# PAGE2_-MCU.net
KiCad netlist of a schematic drawn in Altium Designer
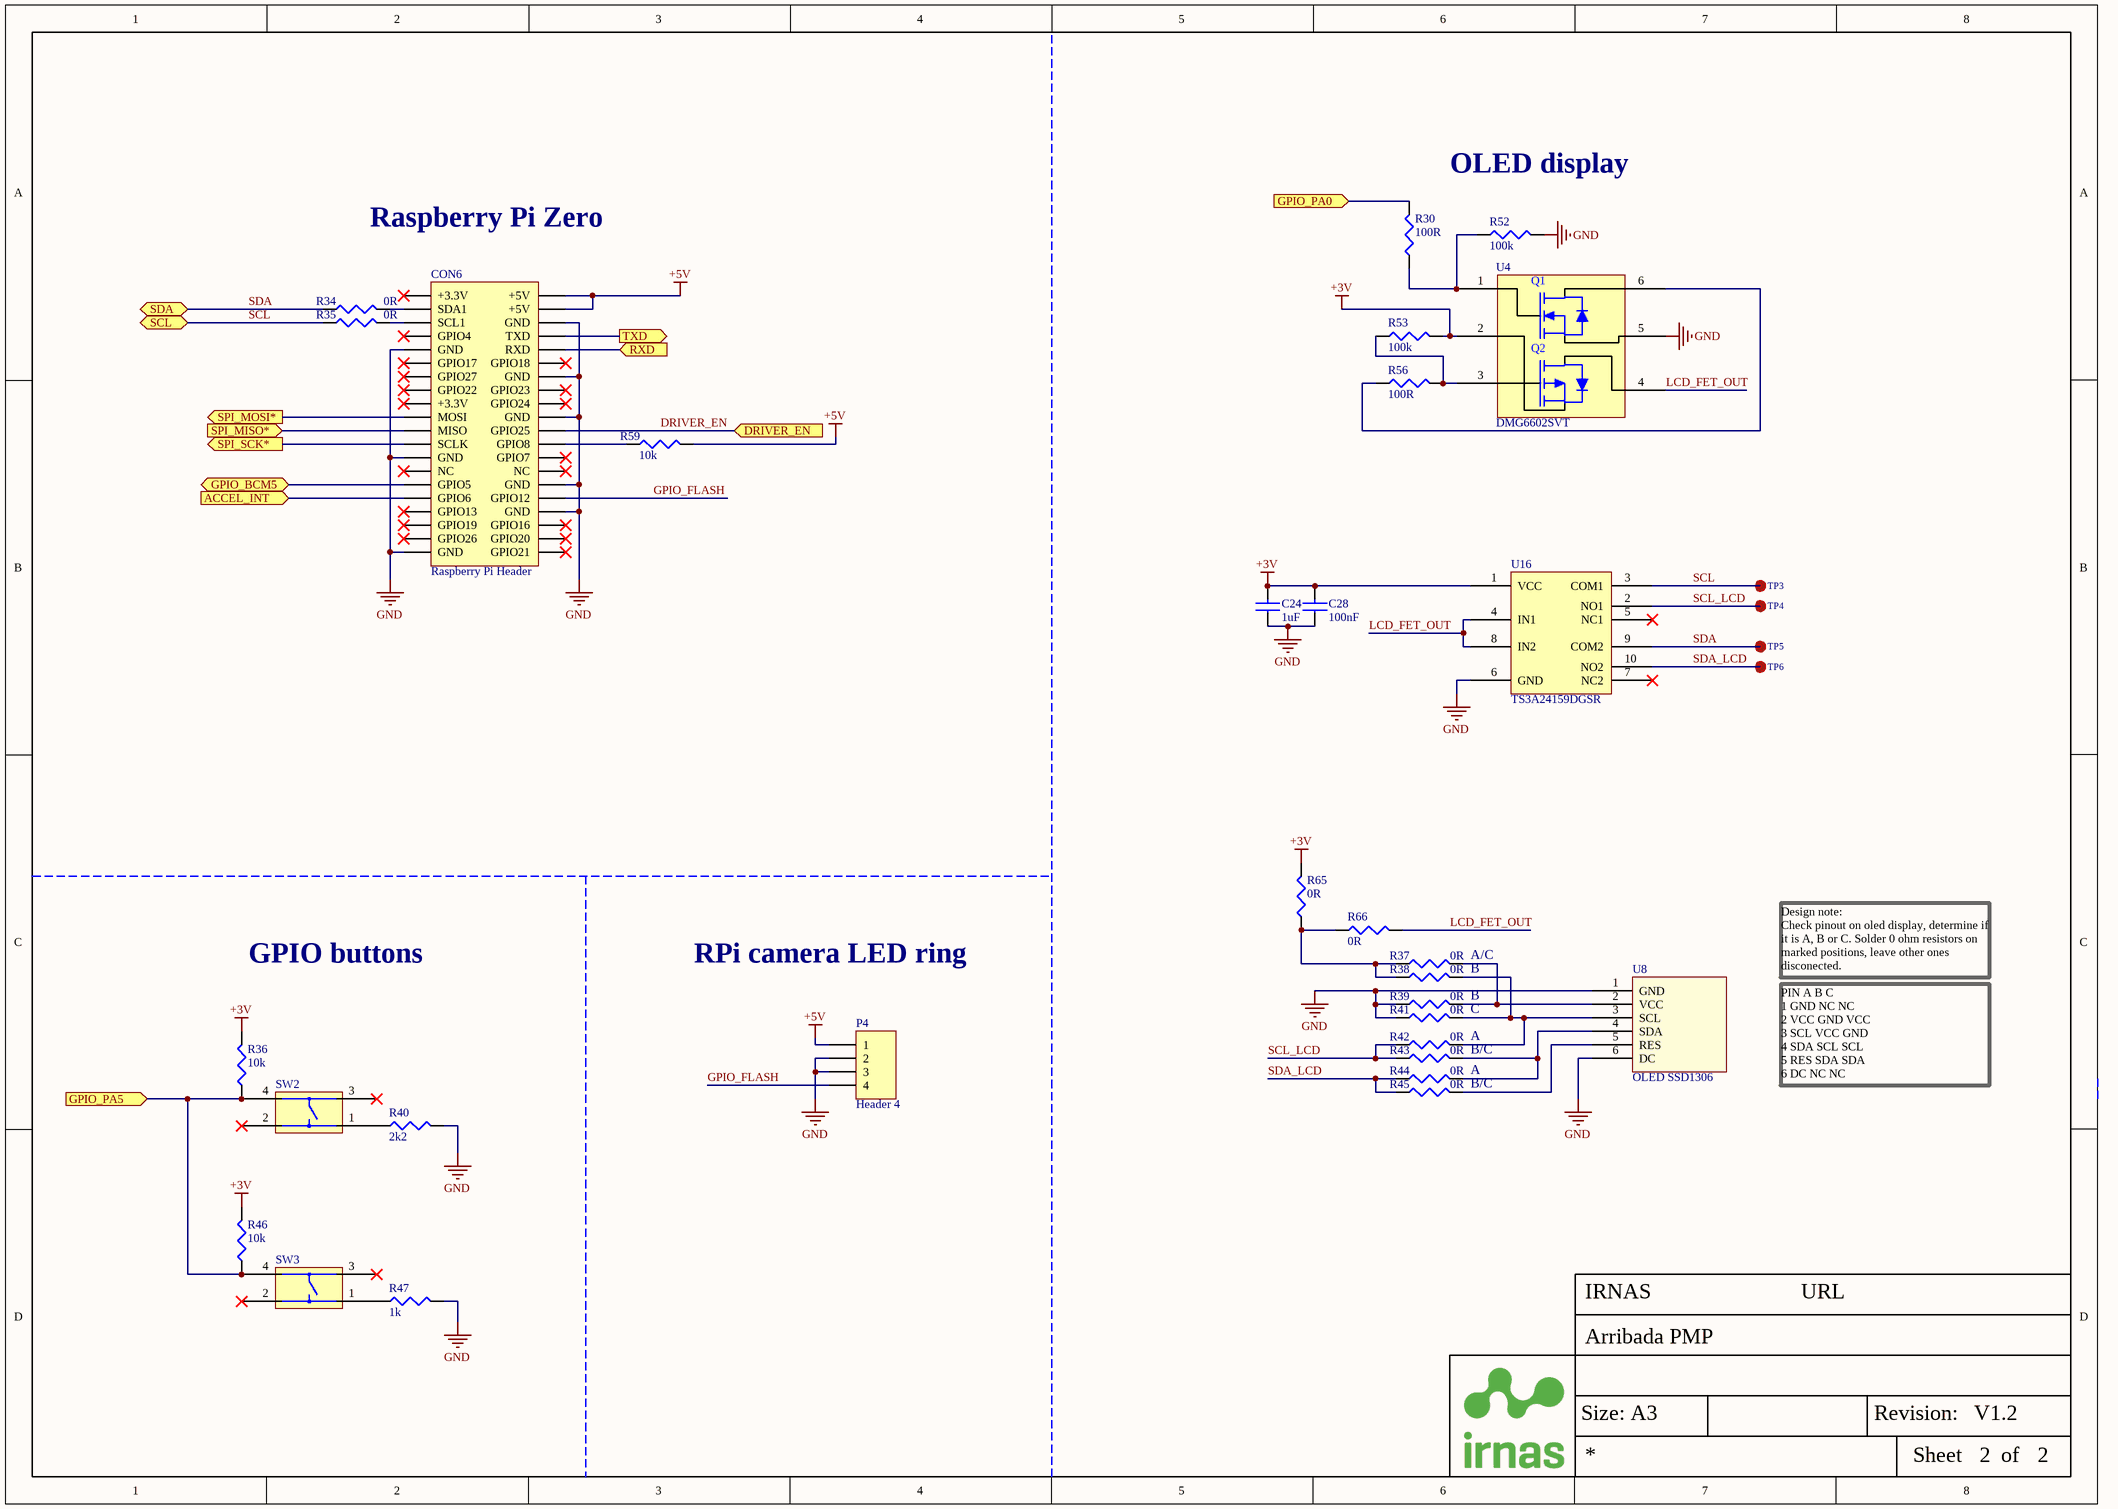
[diagram p0: PAGE2 -MCU.SchDoc]

(export (version "E")
  (design (tool "Eeschema 10.0.6"))
  (components
    (comp (ref "C24")
      (value "1uF")
      (footprint "CAP0603")
      (description "MURATA - GRM188R61H105KAALD - CAP, MLCC, X5R, 1UF, 50V, 0603")
      (fields
        (field (name "MANUFACTURER") "MURATA")
        (field (name "MANUFACTURER PART NUMBER") "GRM188R61H105KAALD")
      )
      (libsource (lib "Passive") (part "C - 1uF"))
    )
    (comp (ref "C28")
      (value "100nF")
      (footprint "CAP0603")
      (description "MURATA - GRM188R71C104KA01J - CAP, MLCC, X7R, 0.1UF, 16V, 0603")
      (fields
        (field (name "MANUFACTURER") "MURATA")
        (field (name "MANUFACTURER PART NUMBER") "GRM188R71C104KA01J")
      )
      (libsource (lib "Passive") (part "C - 100nF"))
    )
    (comp (ref "CON6")
      (value "Raspberry Pi Header")
      (footprint "Connectors:HDR2X20")
      (description "Header, 20-Pin, Dual row")
      (fields (field (name "PUBLISHER") "Altium Limited"))
      (libsource (lib "Connectors") (part "Raspberry Pi Header"))
    )
    (comp (ref "P4")
      (value "Header 4")
      (footprint "HDR1X4")
      (description "Header, 4-Pin")
      (fields (field (name "PUBLISHER") "Altium Limited"))
      (libsource (lib "Miscellaneous Connectors") (part "Header 4"))
    )
    (comp (ref "R30")
      (value "100R")
      (footprint "RES0603")
      (description "MULTICOMP - MC0063W06031100R - RES, THICK FILM, 100R, 1%, 0.063W, 0603")
      (fields
        (field (name "MANUFACTURER") "MULTICOMP")
        (field (name "MANUFACTURER PART NUMBER") "MC0063W06031100R")
      )
      (libsource (lib "Passive") (part "R - 100R"))
    )
    (comp (ref "R34")
      (value "0R")
      (footprint "RES0603")
      (description "BOURNS - CR0603-J/-000ELF - RES, THICK FILM, 0R, 5%, 0.1W, 0603")
      (fields
        (field (name "MANUFACTURER") "BOURNS")
        (field (name "MANUFACTURER PART NUMBER") "CR0603-J/-000ELF")
      )
      (libsource (lib "Passive") (part "R - 0R"))
    )
    (comp (ref "R35")
      (value "0R")
      (footprint "RES0603")
      (description "BOURNS - CR0603-J/-000ELF - RES, THICK FILM, 0R, 5%, 0.1W, 0603")
      (fields
        (field (name "MANUFACTURER") "BOURNS")
        (field (name "MANUFACTURER PART NUMBER") "CR0603-J/-000ELF")
      )
      (libsource (lib "Passive") (part "R - 0R"))
    )
    (comp (ref "R36")
      (value "10k")
      (footprint "RES0603")
      (description "MULTICOMP - MCMR06X103 JTL - RES, CERAMIC, 10K, 5%, 0.1W, 0603")
      (fields
        (field (name "MANUFACTURER") "MULTICOMP")
        (field (name "MANUFACTURER PART NUMBER") "MCMR06X103 JTL")
      )
      (libsource (lib "Passive") (part "R - 10k"))
    )
    (comp (ref "R37")
      (value "0R")
      (footprint "RES0603")
      (description "BOURNS - CR0603-J/-000ELF - RES, THICK FILM, 0R, 5%, 0.1W, 0603")
      (fields
        (field (name "MANUFACTURER") "BOURNS")
        (field (name "MANUFACTURER PART NUMBER") "CR0603-J/-000ELF")
      )
      (libsource (lib "Passive") (part "R - 0R"))
    )
    (comp (ref "R38")
      (value "0R")
      (footprint "RES0603")
      (description "BOURNS - CR0603-J/-000ELF - RES, THICK FILM, 0R, 5%, 0.1W, 0603")
      (fields
        (field (name "MANUFACTURER") "BOURNS")
        (field (name "MANUFACTURER PART NUMBER") "CR0603-J/-000ELF")
      )
      (libsource (lib "Passive") (part "R - 0R"))
    )
    (comp (ref "R39")
      (value "0R")
      (footprint "RES0603")
      (description "BOURNS - CR0603-J/-000ELF - RES, THICK FILM, 0R, 5%, 0.1W, 0603")
      (fields
        (field (name "MANUFACTURER") "BOURNS")
        (field (name "MANUFACTURER PART NUMBER") "CR0603-J/-000ELF")
      )
      (libsource (lib "Passive") (part "R - 0R"))
    )
    (comp (ref "R40")
      (value "2k2")
      (footprint "RES0603")
      (description "MULTICOMP - MCMR06X2201FTL - RES, CERAMIC, 2K2, 1%, 0.1W, 0603")
      (fields
        (field (name "MANUFACTURER") "MULTICOMP")
        (field (name "MANUFACTURER PART NUMBER") "MCMR06X2201FTL")
      )
      (libsource (lib "Passive") (part "R - 2k2"))
    )
    (comp (ref "R41")
      (value "0R")
      (footprint "RES0603")
      (description "BOURNS - CR0603-J/-000ELF - RES, THICK FILM, 0R, 5%, 0.1W, 0603")
      (fields
        (field (name "MANUFACTURER") "BOURNS")
        (field (name "MANUFACTURER PART NUMBER") "CR0603-J/-000ELF")
      )
      (libsource (lib "Passive") (part "R - 0R"))
    )
    (comp (ref "R42")
      (value "0R")
      (footprint "RES0603")
      (description "BOURNS - CR0603-J/-000ELF - RES, THICK FILM, 0R, 5%, 0.1W, 0603")
      (fields
        (field (name "MANUFACTURER") "BOURNS")
        (field (name "MANUFACTURER PART NUMBER") "CR0603-J/-000ELF")
      )
      (libsource (lib "Passive") (part "R - 0R"))
    )
    (comp (ref "R43")
      (value "0R")
      (footprint "RES0603")
      (description "BOURNS - CR0603-J/-000ELF - RES, THICK FILM, 0R, 5%, 0.1W, 0603")
      (fields
        (field (name "MANUFACTURER") "BOURNS")
        (field (name "MANUFACTURER PART NUMBER") "CR0603-J/-000ELF")
      )
      (libsource (lib "Passive") (part "R - 0R"))
    )
    (comp (ref "R44")
      (value "0R")
      (footprint "RES0603")
      (description "BOURNS - CR0603-J/-000ELF - RES, THICK FILM, 0R, 5%, 0.1W, 0603")
      (fields
        (field (name "MANUFACTURER") "BOURNS")
        (field (name "MANUFACTURER PART NUMBER") "CR0603-J/-000ELF")
      )
      (libsource (lib "Passive") (part "R - 0R"))
    )
    (comp (ref "R45")
      (value "0R")
      (footprint "RES0603")
      (description "BOURNS - CR0603-J/-000ELF - RES, THICK FILM, 0R, 5%, 0.1W, 0603")
      (fields
        (field (name "MANUFACTURER") "BOURNS")
        (field (name "MANUFACTURER PART NUMBER") "CR0603-J/-000ELF")
      )
      (libsource (lib "Passive") (part "R - 0R"))
    )
    (comp (ref "R46")
      (value "10k")
      (footprint "RES0603")
      (description "MULTICOMP - MCMR06X103 JTL - RES, CERAMIC, 10K, 5%, 0.1W, 0603")
      (fields
        (field (name "MANUFACTURER") "MULTICOMP")
        (field (name "MANUFACTURER PART NUMBER") "MCMR06X103 JTL")
      )
      (libsource (lib "Passive") (part "R - 10k"))
    )
    (comp (ref "R47")
      (value "1k")
      (footprint "RES0603")
      (description "MULTICOMP - MCMR06X102 JTL - RES, CERAMIC, 1K, 5%, 0.1W, 0603")
      (fields
        (field (name "MANUFACTURER") "MULTICOMP")
        (field (name "MANUFACTURER PART NUMBER") "MCMR06X102 JTL")
      )
      (libsource (lib "Passive") (part "R - 1k"))
    )
    (comp (ref "R52")
      (value "100k")
      (footprint "RES0603")
      (description "MULTICOMP - MCMR06X104 JTL - RES, CERAMIC, 100K, 5%, 0.1W, 0603")
      (fields
        (field (name "MANUFACTURER") "MULTICOMP")
        (field (name "MANUFACTURER PART NUMBER") "MCMR06X104 JTL")
      )
      (libsource (lib "Passive") (part "R - 100k"))
    )
    (comp (ref "R53")
      (value "100k")
      (footprint "RES0603")
      (description "MULTICOMP - MCMR06X104 JTL - RES, CERAMIC, 100K, 5%, 0.1W, 0603")
      (fields
        (field (name "MANUFACTURER") "MULTICOMP")
        (field (name "MANUFACTURER PART NUMBER") "MCMR06X104 JTL")
      )
      (libsource (lib "Passive") (part "R - 100k"))
    )
    (comp (ref "R56")
      (value "100R")
      (footprint "RES0603")
      (description "MULTICOMP - MC0063W06031100R - RES, THICK FILM, 100R, 1%, 0.063W, 0603")
      (fields
        (field (name "MANUFACTURER") "MULTICOMP")
        (field (name "MANUFACTURER PART NUMBER") "MC0063W06031100R")
      )
      (libsource (lib "Passive") (part "R - 100R"))
    )
    (comp (ref "R59")
      (value "10k")
      (footprint "RES0603")
      (description "MULTICOMP - MCMR06X103 JTL - RES, CERAMIC, 10K, 5%, 0.1W, 0603")
      (fields
        (field (name "MANUFACTURER") "MULTICOMP")
        (field (name "MANUFACTURER PART NUMBER") "MCMR06X103 JTL")
      )
      (libsource (lib "Passive") (part "R - 10k"))
    )
    (comp (ref "R65")
      (value "0R")
      (footprint "RES0603")
      (description "BOURNS - CR0603-J/-000ELF - RES, THICK FILM, 0R, 5%, 0.1W, 0603")
      (fields
        (field (name "MANUFACTURER") "BOURNS")
        (field (name "MANUFACTURER PART NUMBER") "CR0603-J/-000ELF")
      )
      (libsource (lib "Passive") (part "R - 0R"))
    )
    (comp (ref "R66")
      (value "0R")
      (footprint "RES0603")
      (description "BOURNS - CR0603-J/-000ELF - RES, THICK FILM, 0R, 5%, 0.1W, 0603")
      (fields
        (field (name "MANUFACTURER") "BOURNS")
        (field (name "MANUFACTURER PART NUMBER") "CR0603-J/-000ELF")
      )
      (libsource (lib "Passive") (part "R - 0R"))
    )
    (comp (ref "SW2")
      (value "BTN - B3F-1070")
      (footprint "BTN B3F-1070")
      (description "Tactile Switch, B3F Series, Top Actuated, Through Hole, Round Button, 100 gf, 50mA at 24VDC")
      (libsource (lib "Mechanical") (part "BTN - B3F-1070"))
    )
    (comp (ref "SW3")
      (value "BTN - B3F-1070")
      (footprint "BTN B3F-1070")
      (description "Tactile Switch, B3F Series, Top Actuated, Through Hole, Round Button, 100 gf, 50mA at 24VDC")
      (libsource (lib "Mechanical") (part "BTN - B3F-1070"))
    )
    (comp (ref "TP3")
      (value "TestPoint")
      (footprint "Passive:TestPoint:1.2x1.2mm")
      (description "TEST POINT ROUND SMD")
      (libsource (lib "Passive") (part "TestPoint"))
    )
    (comp (ref "TP4")
      (value "TestPoint")
      (footprint "Passive:TestPoint:1.2x1.2mm")
      (description "TEST POINT ROUND SMD")
      (libsource (lib "Passive") (part "TestPoint"))
    )
    (comp (ref "TP5")
      (value "TestPoint")
      (footprint "Passive:TestPoint:1.2x1.2mm")
      (description "TEST POINT ROUND SMD")
      (libsource (lib "Passive") (part "TestPoint"))
    )
    (comp (ref "TP6")
      (value "TestPoint")
      (footprint "Passive:TestPoint:1.2x1.2mm")
      (description "TEST POINT ROUND SMD")
      (libsource (lib "Passive") (part "TestPoint"))
    )
    (comp (ref "U4")
      (value "DMG6602SVT")
      (footprint "TSOT26")
      (description "Dual MOSFET, N and P Channel, 3.4 A, 30 V, 0.038 ohm, 10 V, 1 V")
      (libsource (lib "Active") (part "T_M - DMG6602SVT"))
    )
    (comp (ref "U8")
      (value "OLED SSD1306")
      (footprint "OLED SSD1306")
      (libsource (lib "oled") (part "OLED SSD1306"))
    )
    (comp (ref "U16")
      (value "TS3A24159DGSR")
      (footprint "VSSOP-10")
      (description "Analogue Switch, 2 Channels, SPDT, 0.34 ohm, 1.65V to 3.6V, VSSOP, 10 Pins")
      (libsource (lib "Active") (part "INT - TS3A24159DGSR"))
    )
  )
  (nets
    (net (code "1") (name "+3V") (class "Default")
      (node (ref "C24") (pin "2") (pinfunction "2_2") (pintype "passive"))
      (node (ref "C28") (pin "2") (pinfunction "2_2") (pintype "passive"))
      (node (ref "R36") (pin "2") (pinfunction "2_2") (pintype "passive"))
      (node (ref "R46") (pin "2") (pinfunction "2_2") (pintype "passive"))
      (node (ref "R53") (pin "2") (pinfunction "2_2") (pintype "passive"))
      (node (ref "R65") (pin "2") (pinfunction "2_2") (pintype "passive"))
      (node (ref "U16") (pin "1") (pinfunction "VCC_1") (pintype "passive"))
      (node (ref "U4") (pin "2") (pinfunction "S2_2") (pintype "open_collector"))
    )
    (net (code "2") (name "+5V") (class "Default")
      (node (ref "CON6") (pin "2") (pinfunction "+5V_2") (pintype "passive"))
      (node (ref "CON6") (pin "4") (pinfunction "+5V_4") (pintype "passive"))
      (node (ref "P4") (pin "1") (pinfunction "1_1") (pintype "passive"))
      (node (ref "R59") (pin "2") (pinfunction "2_2") (pintype "passive"))
    )
    (net (code "3") (name "/ACCEL_INT") (class "Default")
      (node (ref "CON6") (pin "31") (pinfunction "GPIO6_31") (pintype "passive"))
    )
    (net (code "4") (name "/DRIVER_EN") (class "Default")
      (node (ref "CON6") (pin "22") (pinfunction "GPIO25_22") (pintype "passive"))
    )
    (net (code "5") (name "/GPIO_BCM5") (class "Default")
      (node (ref "CON6") (pin "29") (pinfunction "GPIO5_29") (pintype "passive"))
    )
    (net (code "6") (name "/GPIO_FLASH") (class "Default")
      (node (ref "CON6") (pin "32") (pinfunction "GPIO12_32") (pintype "passive"))
      (node (ref "P4") (pin "4") (pinfunction "4_4") (pintype "passive"))
    )
    (net (code "7") (name "/GPIO_PA0") (class "Default")
      (node (ref "R30") (pin "2") (pinfunction "2_2") (pintype "passive"))
    )
    (net (code "8") (name "/GPIO_PA5") (class "Default")
      (node (ref "R36") (pin "1") (pinfunction "1_1") (pintype "passive"))
      (node (ref "R46") (pin "1") (pinfunction "1_1") (pintype "passive"))
      (node (ref "SW2") (pin "4") (pinfunction "4_4") (pintype "passive"))
      (node (ref "SW3") (pin "4") (pinfunction "4_4") (pintype "passive"))
    )
    (net (code "9") (name "/LCD_FET_OUT") (class "Default")
      (node (ref "R66") (pin "2") (pinfunction "2_2") (pintype "passive"))
      (node (ref "U16") (pin "4") (pinfunction "IN1_4") (pintype "passive"))
      (node (ref "U16") (pin "8") (pinfunction "IN2_8") (pintype "passive"))
      (node (ref "U4") (pin "4") (pinfunction "D2_4") (pintype "open_collector"))
    )
    (net (code "10") (name "/RXD") (class "Default")
      (node (ref "CON6") (pin "10") (pinfunction "RXD_10") (pintype "passive"))
    )
    (net (code "11") (name "/SCL") (class "Default")
      (node (ref "R35") (pin "1") (pinfunction "1_1") (pintype "passive"))
      (node (ref "TP3") (pin "0") (pinfunction "0_0") (pintype "passive"))
      (node (ref "U16") (pin "3") (pinfunction "COM1_3") (pintype "passive"))
    )
    (net (code "12") (name "/SCL_LCD") (class "Default")
      (node (ref "R42") (pin "1") (pinfunction "1_1") (pintype "passive"))
      (node (ref "R43") (pin "1") (pinfunction "1_1") (pintype "passive"))
      (node (ref "TP4") (pin "0") (pinfunction "0_0") (pintype "passive"))
      (node (ref "U16") (pin "2") (pinfunction "NO1_2") (pintype "passive"))
    )
    (net (code "13") (name "/SDA") (class "Default")
      (node (ref "R34") (pin "1") (pinfunction "1_1") (pintype "passive"))
      (node (ref "TP5") (pin "0") (pinfunction "0_0") (pintype "passive"))
      (node (ref "U16") (pin "9") (pinfunction "COM2_9") (pintype "passive"))
    )
    (net (code "14") (name "/SDA_LCD") (class "Default")
      (node (ref "R44") (pin "1") (pinfunction "1_1") (pintype "passive"))
      (node (ref "R45") (pin "1") (pinfunction "1_1") (pintype "passive"))
      (node (ref "TP6") (pin "0") (pinfunction "0_0") (pintype "passive"))
      (node (ref "U16") (pin "10") (pinfunction "NO2_10") (pintype "passive"))
    )
    (net (code "15") (name "/SPI_MISO*") (class "Default")
      (node (ref "CON6") (pin "21") (pinfunction "MISO_21") (pintype "passive"))
    )
    (net (code "16") (name "/SPI_MOSI*") (class "Default")
      (node (ref "CON6") (pin "19") (pinfunction "MOSI_19") (pintype "passive"))
    )
    (net (code "17") (name "/SPI_SCK*") (class "Default")
      (node (ref "CON6") (pin "23") (pinfunction "SCLK_23") (pintype "passive"))
    )
    (net (code "18") (name "/TXD") (class "Default")
      (node (ref "CON6") (pin "8") (pinfunction "TXD_8") (pintype "passive"))
    )
    (net (code "19") (name "GND") (class "Default")
      (node (ref "C24") (pin "1") (pinfunction "1_1") (pintype "passive"))
      (node (ref "C28") (pin "1") (pinfunction "1_1") (pintype "passive"))
      (node (ref "CON6") (pin "14") (pinfunction "GND_14") (pintype "passive"))
      (node (ref "CON6") (pin "20") (pinfunction "GND_20") (pintype "passive"))
      (node (ref "CON6") (pin "25") (pinfunction "GND_25") (pintype "passive"))
      (node (ref "CON6") (pin "30") (pinfunction "GND_30") (pintype "passive"))
      (node (ref "CON6") (pin "34") (pinfunction "GND_34") (pintype "passive"))
      (node (ref "CON6") (pin "39") (pinfunction "GND_39") (pintype "passive"))
      (node (ref "CON6") (pin "6") (pinfunction "GND_6") (pintype "passive"))
      (node (ref "CON6") (pin "9") (pinfunction "GND_9") (pintype "passive"))
      (node (ref "P4") (pin "2") (pinfunction "2_2") (pintype "passive"))
      (node (ref "P4") (pin "3") (pinfunction "3_3") (pintype "passive"))
      (node (ref "R39") (pin "1") (pinfunction "1_1") (pintype "passive"))
      (node (ref "R40") (pin "2") (pinfunction "2_2") (pintype "passive"))
      (node (ref "R41") (pin "1") (pinfunction "1_1") (pintype "passive"))
      (node (ref "R47") (pin "2") (pinfunction "2_2") (pintype "passive"))
      (node (ref "R52") (pin "2") (pinfunction "2_2") (pintype "passive"))
      (node (ref "U16") (pin "6") (pinfunction "GND_6") (pintype "passive"))
      (node (ref "U4") (pin "5") (pinfunction "S1_5") (pintype "open_collector"))
      (node (ref "U8") (pin "1") (pinfunction "GND_1") (pintype "passive"))
      (node (ref "U8") (pin "6") (pinfunction "DC_6") (pintype "passive"))
    )
    (net (code "20") (name "Net-(CON6-GPIO8)") (class "Default")
      (node (ref "CON6") (pin "24") (pinfunction "GPIO8_24") (pintype "passive"))
      (node (ref "R59") (pin "1") (pinfunction "1_1") (pintype "passive"))
    )
    (net (code "21") (name "Net-(CON6-SCL1)") (class "Default")
      (node (ref "CON6") (pin "5") (pinfunction "SCL1_5") (pintype "passive"))
      (node (ref "R35") (pin "2") (pinfunction "2_2") (pintype "passive"))
    )
    (net (code "22") (name "Net-(CON6-SDA1)") (class "Default")
      (node (ref "CON6") (pin "3") (pinfunction "SDA1_3") (pintype "passive"))
      (node (ref "R34") (pin "2") (pinfunction "2_2") (pintype "passive"))
    )
    (net (code "23") (name "Net-(R37-Pad1)") (class "Default")
      (node (ref "R37") (pin "1") (pinfunction "1_1") (pintype "passive"))
      (node (ref "R38") (pin "1") (pinfunction "1_1") (pintype "passive"))
      (node (ref "R65") (pin "1") (pinfunction "1_1") (pintype "passive"))
      (node (ref "R66") (pin "1") (pinfunction "1_1") (pintype "passive"))
    )
    (net (code "24") (name "Net-(R40-Pad1)") (class "Default")
      (node (ref "R40") (pin "1") (pinfunction "1_1") (pintype "passive"))
      (node (ref "SW2") (pin "1") (pinfunction "1_1") (pintype "passive"))
    )
    (net (code "25") (name "Net-(R47-Pad1)") (class "Default")
      (node (ref "R47") (pin "1") (pinfunction "1_1") (pintype "passive"))
      (node (ref "SW3") (pin "1") (pinfunction "1_1") (pintype "passive"))
    )
    (net (code "26") (name "Net-(U4-D1)") (class "Default")
      (node (ref "R56") (pin "1") (pinfunction "1_1") (pintype "passive"))
      (node (ref "U4") (pin "6") (pinfunction "D1_6") (pintype "open_collector"))
    )
    (net (code "27") (name "Net-(U4-G1)") (class "Default")
      (node (ref "R30") (pin "1") (pinfunction "1_1") (pintype "passive"))
      (node (ref "R52") (pin "1") (pinfunction "1_1") (pintype "passive"))
      (node (ref "U4") (pin "1") (pinfunction "G1_1") (pintype "open_collector"))
    )
    (net (code "28") (name "Net-(U4-G2)") (class "Default")
      (node (ref "R53") (pin "1") (pinfunction "1_1") (pintype "passive"))
      (node (ref "R56") (pin "2") (pinfunction "2_2") (pintype "passive"))
      (node (ref "U4") (pin "3") (pinfunction "G2_3") (pintype "open_collector"))
    )
    (net (code "29") (name "Net-(U8-RES)") (class "Default")
      (node (ref "R45") (pin "2") (pinfunction "2_2") (pintype "passive"))
      (node (ref "U8") (pin "5") (pinfunction "RES_5") (pintype "passive"))
    )
    (net (code "30") (name "Net-(U8-SCL)") (class "Default")
      (node (ref "R38") (pin "2") (pinfunction "2_2") (pintype "passive"))
      (node (ref "R41") (pin "2") (pinfunction "2_2") (pintype "passive"))
      (node (ref "R42") (pin "2") (pinfunction "2_2") (pintype "passive"))
      (node (ref "U8") (pin "3") (pinfunction "SCL_3") (pintype "passive"))
    )
    (net (code "31") (name "Net-(U8-SDA)") (class "Default")
      (node (ref "R43") (pin "2") (pinfunction "2_2") (pintype "passive"))
      (node (ref "R44") (pin "2") (pinfunction "2_2") (pintype "passive"))
      (node (ref "U8") (pin "4") (pinfunction "SDA_4") (pintype "passive"))
    )
    (net (code "32") (name "Net-(U8-VCC)") (class "Default")
      (node (ref "R37") (pin "2") (pinfunction "2_2") (pintype "passive"))
      (node (ref "R39") (pin "2") (pinfunction "2_2") (pintype "passive"))
      (node (ref "U8") (pin "2") (pinfunction "VCC_2") (pintype "passive"))
    )
    (net (code "33") (name "unconnected-(CON6-+3.3V-Pad1)") (class "Default")
      (node (ref "CON6") (pin "1") (pinfunction "+3.3V_1") (pintype "passive+no_connect"))
    )
    (net (code "34") (name "unconnected-(CON6-+3.3V-Pad17)") (class "Default")
      (node (ref "CON6") (pin "17") (pinfunction "+3.3V_17") (pintype "passive+no_connect"))
    )
    (net (code "35") (name "unconnected-(CON6-GPIO4-Pad7)") (class "Default")
      (node (ref "CON6") (pin "7") (pinfunction "GPIO4_7") (pintype "passive+no_connect"))
    )
    (net (code "36") (name "unconnected-(CON6-GPIO7-Pad26)") (class "Default")
      (node (ref "CON6") (pin "26") (pinfunction "GPIO7_26") (pintype "passive+no_connect"))
    )
    (net (code "37") (name "unconnected-(CON6-GPIO13-Pad33)") (class "Default")
      (node (ref "CON6") (pin "33") (pinfunction "GPIO13_33") (pintype "passive+no_connect"))
    )
    (net (code "38") (name "unconnected-(CON6-GPIO16-Pad36)") (class "Default")
      (node (ref "CON6") (pin "36") (pinfunction "GPIO16_36") (pintype "passive+no_connect"))
    )
    (net (code "39") (name "unconnected-(CON6-GPIO17-Pad11)") (class "Default")
      (node (ref "CON6") (pin "11") (pinfunction "GPIO17_11") (pintype "passive+no_connect"))
    )
    (net (code "40") (name "unconnected-(CON6-GPIO18-Pad12)") (class "Default")
      (node (ref "CON6") (pin "12") (pinfunction "GPIO18_12") (pintype "passive+no_connect"))
    )
    (net (code "41") (name "unconnected-(CON6-GPIO19-Pad35)") (class "Default")
      (node (ref "CON6") (pin "35") (pinfunction "GPIO19_35") (pintype "passive+no_connect"))
    )
    (net (code "42") (name "unconnected-(CON6-GPIO20-Pad38)") (class "Default")
      (node (ref "CON6") (pin "38") (pinfunction "GPIO20_38") (pintype "passive+no_connect"))
    )
    (net (code "43") (name "unconnected-(CON6-GPIO21-Pad40)") (class "Default")
      (node (ref "CON6") (pin "40") (pinfunction "GPIO21_40") (pintype "passive+no_connect"))
    )
    (net (code "44") (name "unconnected-(CON6-GPIO22-Pad15)") (class "Default")
      (node (ref "CON6") (pin "15") (pinfunction "GPIO22_15") (pintype "passive+no_connect"))
    )
    (net (code "45") (name "unconnected-(CON6-GPIO23-Pad16)") (class "Default")
      (node (ref "CON6") (pin "16") (pinfunction "GPIO23_16") (pintype "passive+no_connect"))
    )
    (net (code "46") (name "unconnected-(CON6-GPIO24-Pad18)") (class "Default")
      (node (ref "CON6") (pin "18") (pinfunction "GPIO24_18") (pintype "passive+no_connect"))
    )
    (net (code "47") (name "unconnected-(CON6-GPIO26-Pad37)") (class "Default")
      (node (ref "CON6") (pin "37") (pinfunction "GPIO26_37") (pintype "passive+no_connect"))
    )
    (net (code "48") (name "unconnected-(CON6-GPIO27-Pad13)") (class "Default")
      (node (ref "CON6") (pin "13") (pinfunction "GPIO27_13") (pintype "passive+no_connect"))
    )
    (net (code "49") (name "unconnected-(CON6-NC-Pad27)") (class "Default")
      (node (ref "CON6") (pin "27") (pinfunction "NC_27") (pintype "passive+no_connect"))
    )
    (net (code "50") (name "unconnected-(CON6-NC-Pad28)") (class "Default")
      (node (ref "CON6") (pin "28") (pinfunction "NC_28") (pintype "passive+no_connect"))
    )
    (net (code "51") (name "unconnected-(SW2-Pad2)") (class "Default")
      (node (ref "SW2") (pin "2") (pinfunction "2_2") (pintype "passive+no_connect"))
    )
    (net (code "52") (name "unconnected-(SW2-Pad3)") (class "Default")
      (node (ref "SW2") (pin "3") (pinfunction "3_3") (pintype "passive+no_connect"))
    )
    (net (code "53") (name "unconnected-(SW3-Pad2)") (class "Default")
      (node (ref "SW3") (pin "2") (pinfunction "2_2") (pintype "passive+no_connect"))
    )
    (net (code "54") (name "unconnected-(SW3-Pad3)") (class "Default")
      (node (ref "SW3") (pin "3") (pinfunction "3_3") (pintype "passive+no_connect"))
    )
    (net (code "55") (name "unconnected-(U16-NC1-Pad5)") (class "Default")
      (node (ref "U16") (pin "5") (pinfunction "NC1_5") (pintype "passive+no_connect"))
    )
    (net (code "56") (name "unconnected-(U16-NC2-Pad7)") (class "Default")
      (node (ref "U16") (pin "7") (pinfunction "NC2_7") (pintype "passive+no_connect"))
    )
  )
)
